# Current_Voltage_Dividers.net
KiCad netlist of a schematic drawn in Altium Designer
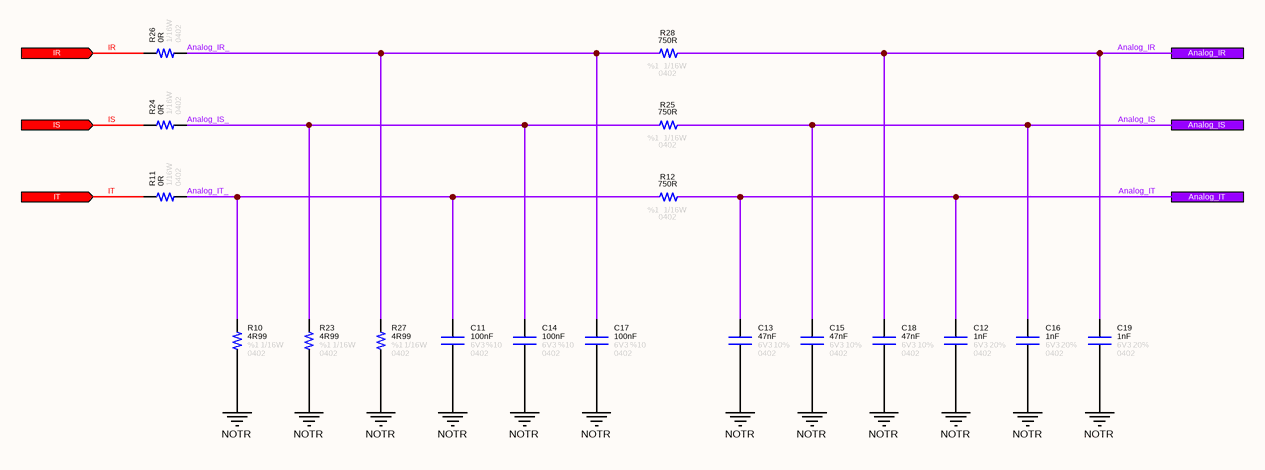
[diagram p0: Current Voltage Dividers.SchDoc]

(export (version "E")
  (design (tool "Eeschema 10.0.6"))
  (components
    (comp (ref "C11")
      (value "100nF")
      (footprint "CAPACITOR_0402")
      (description "Capacitor - 100nF [0402-6V3] (Ceramic)")
      (fields
        (field (name "MANUFACTURER PART NUMBER") "04026D104KAT4A")
        (field (name "TOLERANCE") "%10")
        (field (name "VOLTAGE") "6V3")
        (field (name "CASE") "0402")
        (field (name "Comment") "Capacitor - 100nF [0402] (Ceramic)")
      )
      (libsource (lib "Akkoyun") (part "Capacitor - 100nF [0402-6V3]"))
    )
    (comp (ref "C12")
      (value "1nF")
      (footprint "CAPACITOR_0402")
      (description "Capacitor - 1nF [0402] (Ceramic)")
      (fields
        (field (name "MANUFACTURER PART NUMBER") "04026C102MAT2A")
        (field (name "TOLERANCE") "20%")
        (field (name "CASE") "0402")
        (field (name "VOLTAGE") "6V3")
      )
      (libsource (lib "Akkoyun") (part "Capacitor - 1nF [0402-6V3]"))
    )
    (comp (ref "C13")
      (value "47nF")
      (footprint "CAPACITOR_0402")
      (description "Multilayer Ceramic Capacitors - SMD - 6.3V 47nF X7R 0402 10%")
      (fields
        (field (name "MANUFACTURER PART NUMBER") "04026C473KAT2A")
        (field (name "TOLERANCE") "10%")
        (field (name "CASE") "0402")
        (field (name "VOLTAGE") "6V3")
        (field (name "Comment") "Capacitor - 47nF [0402] (Ceramic)")
      )
      (libsource (lib "Akkoyun") (part "Capacitor - 47nF [0402-6V3]"))
    )
    (comp (ref "C14")
      (value "100nF")
      (footprint "CAPACITOR_0402")
      (description "Capacitor - 100nF [0402-6V3] (Ceramic)")
      (fields
        (field (name "MANUFACTURER PART NUMBER") "04026D104KAT4A")
        (field (name "TOLERANCE") "%10")
        (field (name "VOLTAGE") "6V3")
        (field (name "CASE") "0402")
        (field (name "Comment") "Capacitor - 100nF [0402] (Ceramic)")
      )
      (libsource (lib "Akkoyun") (part "Capacitor - 100nF [0402-6V3]"))
    )
    (comp (ref "C15")
      (value "47nF")
      (footprint "CAPACITOR_0402")
      (description "Multilayer Ceramic Capacitors - SMD - 6.3V 47nF X7R 0402 10%")
      (fields
        (field (name "MANUFACTURER PART NUMBER") "04026C473KAT2A")
        (field (name "TOLERANCE") "10%")
        (field (name "CASE") "0402")
        (field (name "VOLTAGE") "6V3")
        (field (name "Comment") "Capacitor - 47nF [0402] (Ceramic)")
      )
      (libsource (lib "Akkoyun") (part "Capacitor - 47nF [0402-6V3]"))
    )
    (comp (ref "C16")
      (value "1nF")
      (footprint "CAPACITOR_0402")
      (description "Capacitor - 1nF [0402] (Ceramic)")
      (fields
        (field (name "MANUFACTURER PART NUMBER") "04026C102MAT2A")
        (field (name "TOLERANCE") "20%")
        (field (name "CASE") "0402")
        (field (name "VOLTAGE") "6V3")
      )
      (libsource (lib "Akkoyun") (part "Capacitor - 1nF [0402-6V3]"))
    )
    (comp (ref "C17")
      (value "100nF")
      (footprint "CAPACITOR_0402")
      (description "Capacitor - 100nF [0402-6V3] (Ceramic)")
      (fields
        (field (name "MANUFACTURER PART NUMBER") "04026D104KAT4A")
        (field (name "TOLERANCE") "%10")
        (field (name "VOLTAGE") "6V3")
        (field (name "CASE") "0402")
        (field (name "Comment") "Capacitor - 100nF [0402] (Ceramic)")
      )
      (libsource (lib "Akkoyun") (part "Capacitor - 100nF [0402-6V3]"))
    )
    (comp (ref "C18")
      (value "47nF")
      (footprint "CAPACITOR_0402")
      (description "Multilayer Ceramic Capacitors - SMD - 6.3V 47nF X7R 0402 10%")
      (fields
        (field (name "MANUFACTURER PART NUMBER") "04026C473KAT2A")
        (field (name "TOLERANCE") "10%")
        (field (name "CASE") "0402")
        (field (name "VOLTAGE") "6V3")
        (field (name "Comment") "Capacitor - 47nF [0402] (Ceramic)")
      )
      (libsource (lib "Akkoyun") (part "Capacitor - 47nF [0402-6V3]"))
    )
    (comp (ref "C19")
      (value "1nF")
      (footprint "CAPACITOR_0402")
      (description "Capacitor - 1nF [0402] (Ceramic)")
      (fields
        (field (name "MANUFACTURER PART NUMBER") "04026C102MAT2A")
        (field (name "TOLERANCE") "20%")
        (field (name "CASE") "0402")
        (field (name "VOLTAGE") "6V3")
      )
      (libsource (lib "Akkoyun") (part "Capacitor - 1nF [0402-6V3]"))
    )
    (comp (ref "R10")
      (value "4R99")
      (footprint "RESISTOR_0402")
      (description "Thick Film Resistors - SMD 1/16 W 33 Ohm 1%")
      (fields
        (field (name "MANUFACTURER PART NUMBER") "CRT0402-FZ-4R99GLF")
        (field (name "CASE") "0402")
        (field (name "TOLERANCE") "%1")
        (field (name "POWER") "1/16W")
        (field (name "Comment") "4R99 - 0402 - %1 - 1/16W")
      )
      (libsource (lib "Akkoyun") (part "Resistor - 4R99 [0402]"))
    )
    (comp (ref "R11")
      (value "0R")
      (footprint "RESISTOR_0402")
      (description "Thick Film Resistors - SMD 1/16 W 0 Ohm")
      (fields
        (field (name "MANUFACTURER PART NUMBER") "CRCW04020000Z0ED")
        (field (name "CASE") "0402")
        (field (name "POWER") "1/16W")
        (field (name "Comment") "0R - 0402 - %1 - 1/16W")
      )
      (libsource (lib "Akkoyun") (part "Resistor - 0R [0402]"))
    )
    (comp (ref "R12")
      (value "750R")
      (footprint "RESISTOR_0402")
      (description "Thick Film Resistors - SMD 1/16 W 750 Ohm 1%")
      (fields
        (field (name "MANUFACTURER PART NUMBER") "CRCW0402750RFKED")
        (field (name "CASE") "0402")
        (field (name "TOLERANCE") "%1")
        (field (name "POWER") "1/16W")
        (field (name "Comment") "750R - 0402 - %1 - 1/16W")
      )
      (libsource (lib "Akkoyun") (part "Resistor - 750R [0402]"))
    )
    (comp (ref "R23")
      (value "4R99")
      (footprint "RESISTOR_0402")
      (description "Thick Film Resistors - SMD 1/16 W 33 Ohm 1%")
      (fields
        (field (name "MANUFACTURER PART NUMBER") "CRT0402-FZ-4R99GLF")
        (field (name "CASE") "0402")
        (field (name "TOLERANCE") "%1")
        (field (name "POWER") "1/16W")
        (field (name "Comment") "4R99 - 0402 - %1 - 1/16W")
      )
      (libsource (lib "Akkoyun") (part "Resistor - 4R99 [0402]"))
    )
    (comp (ref "R24")
      (value "0R")
      (footprint "RESISTOR_0402")
      (description "Thick Film Resistors - SMD 1/16 W 0 Ohm")
      (fields
        (field (name "MANUFACTURER PART NUMBER") "CRCW04020000Z0ED")
        (field (name "CASE") "0402")
        (field (name "POWER") "1/16W")
        (field (name "Comment") "0R - 0402 - %1 - 1/16W")
      )
      (libsource (lib "Akkoyun") (part "Resistor - 0R [0402]"))
    )
    (comp (ref "R25")
      (value "750R")
      (footprint "RESISTOR_0402")
      (description "Thick Film Resistors - SMD 1/16 W 750 Ohm 1%")
      (fields
        (field (name "MANUFACTURER PART NUMBER") "CRCW0402750RFKED")
        (field (name "CASE") "0402")
        (field (name "TOLERANCE") "%1")
        (field (name "POWER") "1/16W")
        (field (name "Comment") "750R - 0402 - %1 - 1/16W")
      )
      (libsource (lib "Akkoyun") (part "Resistor - 750R [0402]"))
    )
    (comp (ref "R26")
      (value "0R")
      (footprint "RESISTOR_0402")
      (description "Thick Film Resistors - SMD 1/16 W 0 Ohm")
      (fields
        (field (name "MANUFACTURER PART NUMBER") "CRCW04020000Z0ED")
        (field (name "CASE") "0402")
        (field (name "POWER") "1/16W")
        (field (name "Comment") "0R - 0402 - %1 - 1/16W")
      )
      (libsource (lib "Akkoyun") (part "Resistor - 0R [0402]"))
    )
    (comp (ref "R27")
      (value "4R99")
      (footprint "RESISTOR_0402")
      (description "Thick Film Resistors - SMD 1/16 W 33 Ohm 1%")
      (fields
        (field (name "MANUFACTURER PART NUMBER") "CRT0402-FZ-4R99GLF")
        (field (name "CASE") "0402")
        (field (name "TOLERANCE") "%1")
        (field (name "POWER") "1/16W")
        (field (name "Comment") "4R99 - 0402 - %1 - 1/16W")
      )
      (libsource (lib "Akkoyun") (part "Resistor - 4R99 [0402]"))
    )
    (comp (ref "R28")
      (value "750R")
      (footprint "RESISTOR_0402")
      (description "Thick Film Resistors - SMD 1/16 W 750 Ohm 1%")
      (fields
        (field (name "MANUFACTURER PART NUMBER") "CRCW0402750RFKED")
        (field (name "CASE") "0402")
        (field (name "TOLERANCE") "%1")
        (field (name "POWER") "1/16W")
        (field (name "Comment") "750R - 0402 - %1 - 1/16W")
      )
      (libsource (lib "Akkoyun") (part "Resistor - 750R [0402]"))
    )
  )
  (nets
    (net (code "1") (name "/Analog_IR") (class "Default")
      (node (ref "C18") (pin "2") (pinfunction "2_2") (pintype "passive"))
      (node (ref "C19") (pin "2") (pinfunction "2_2") (pintype "passive"))
      (node (ref "R28") (pin "1") (pinfunction "1_1") (pintype "passive"))
    )
    (net (code "2") (name "/Analog_IR_") (class "Default")
      (node (ref "C17") (pin "2") (pinfunction "2_2") (pintype "passive"))
      (node (ref "R26") (pin "1") (pinfunction "1_1") (pintype "passive"))
      (node (ref "R27") (pin "2") (pinfunction "2_2") (pintype "passive"))
      (node (ref "R28") (pin "2") (pinfunction "2_2") (pintype "passive"))
    )
    (net (code "3") (name "/Analog_IS") (class "Default")
      (node (ref "C15") (pin "2") (pinfunction "2_2") (pintype "passive"))
      (node (ref "C16") (pin "2") (pinfunction "2_2") (pintype "passive"))
      (node (ref "R25") (pin "1") (pinfunction "1_1") (pintype "passive"))
    )
    (net (code "4") (name "/Analog_IS_") (class "Default")
      (node (ref "C14") (pin "2") (pinfunction "2_2") (pintype "passive"))
      (node (ref "R23") (pin "2") (pinfunction "2_2") (pintype "passive"))
      (node (ref "R24") (pin "1") (pinfunction "1_1") (pintype "passive"))
      (node (ref "R25") (pin "2") (pinfunction "2_2") (pintype "passive"))
    )
    (net (code "5") (name "/Analog_IT") (class "Default")
      (node (ref "C12") (pin "2") (pinfunction "2_2") (pintype "passive"))
      (node (ref "C13") (pin "2") (pinfunction "2_2") (pintype "passive"))
      (node (ref "R12") (pin "1") (pinfunction "1_1") (pintype "passive"))
    )
    (net (code "6") (name "/Analog_IT_") (class "Default")
      (node (ref "C11") (pin "2") (pinfunction "2_2") (pintype "passive"))
      (node (ref "R10") (pin "2") (pinfunction "2_2") (pintype "passive"))
      (node (ref "R11") (pin "1") (pinfunction "1_1") (pintype "passive"))
      (node (ref "R12") (pin "2") (pinfunction "2_2") (pintype "passive"))
    )
    (net (code "7") (name "/IR") (class "Default")
      (node (ref "R26") (pin "2") (pinfunction "2_2") (pintype "passive"))
    )
    (net (code "8") (name "/IS") (class "Default")
      (node (ref "R24") (pin "2") (pinfunction "2_2") (pintype "passive"))
    )
    (net (code "9") (name "/IT") (class "Default")
      (node (ref "R11") (pin "2") (pinfunction "2_2") (pintype "passive"))
    )
    (net (code "10") (name "NOTR") (class "Default")
      (node (ref "C11") (pin "1") (pinfunction "1_1") (pintype "passive"))
      (node (ref "C12") (pin "1") (pinfunction "1_1") (pintype "passive"))
      (node (ref "C13") (pin "1") (pinfunction "1_1") (pintype "passive"))
      (node (ref "C14") (pin "1") (pinfunction "1_1") (pintype "passive"))
      (node (ref "C15") (pin "1") (pinfunction "1_1") (pintype "passive"))
      (node (ref "C16") (pin "1") (pinfunction "1_1") (pintype "passive"))
      (node (ref "C17") (pin "1") (pinfunction "1_1") (pintype "passive"))
      (node (ref "C18") (pin "1") (pinfunction "1_1") (pintype "passive"))
      (node (ref "C19") (pin "1") (pinfunction "1_1") (pintype "passive"))
      (node (ref "R10") (pin "1") (pinfunction "1_1") (pintype "passive"))
      (node (ref "R23") (pin "1") (pinfunction "1_1") (pintype "passive"))
      (node (ref "R27") (pin "1") (pinfunction "1_1") (pintype "passive"))
    )
  )
)
